# 1-voice_3_3.net
KiCad netlist of a schematic drawn in EAGLE
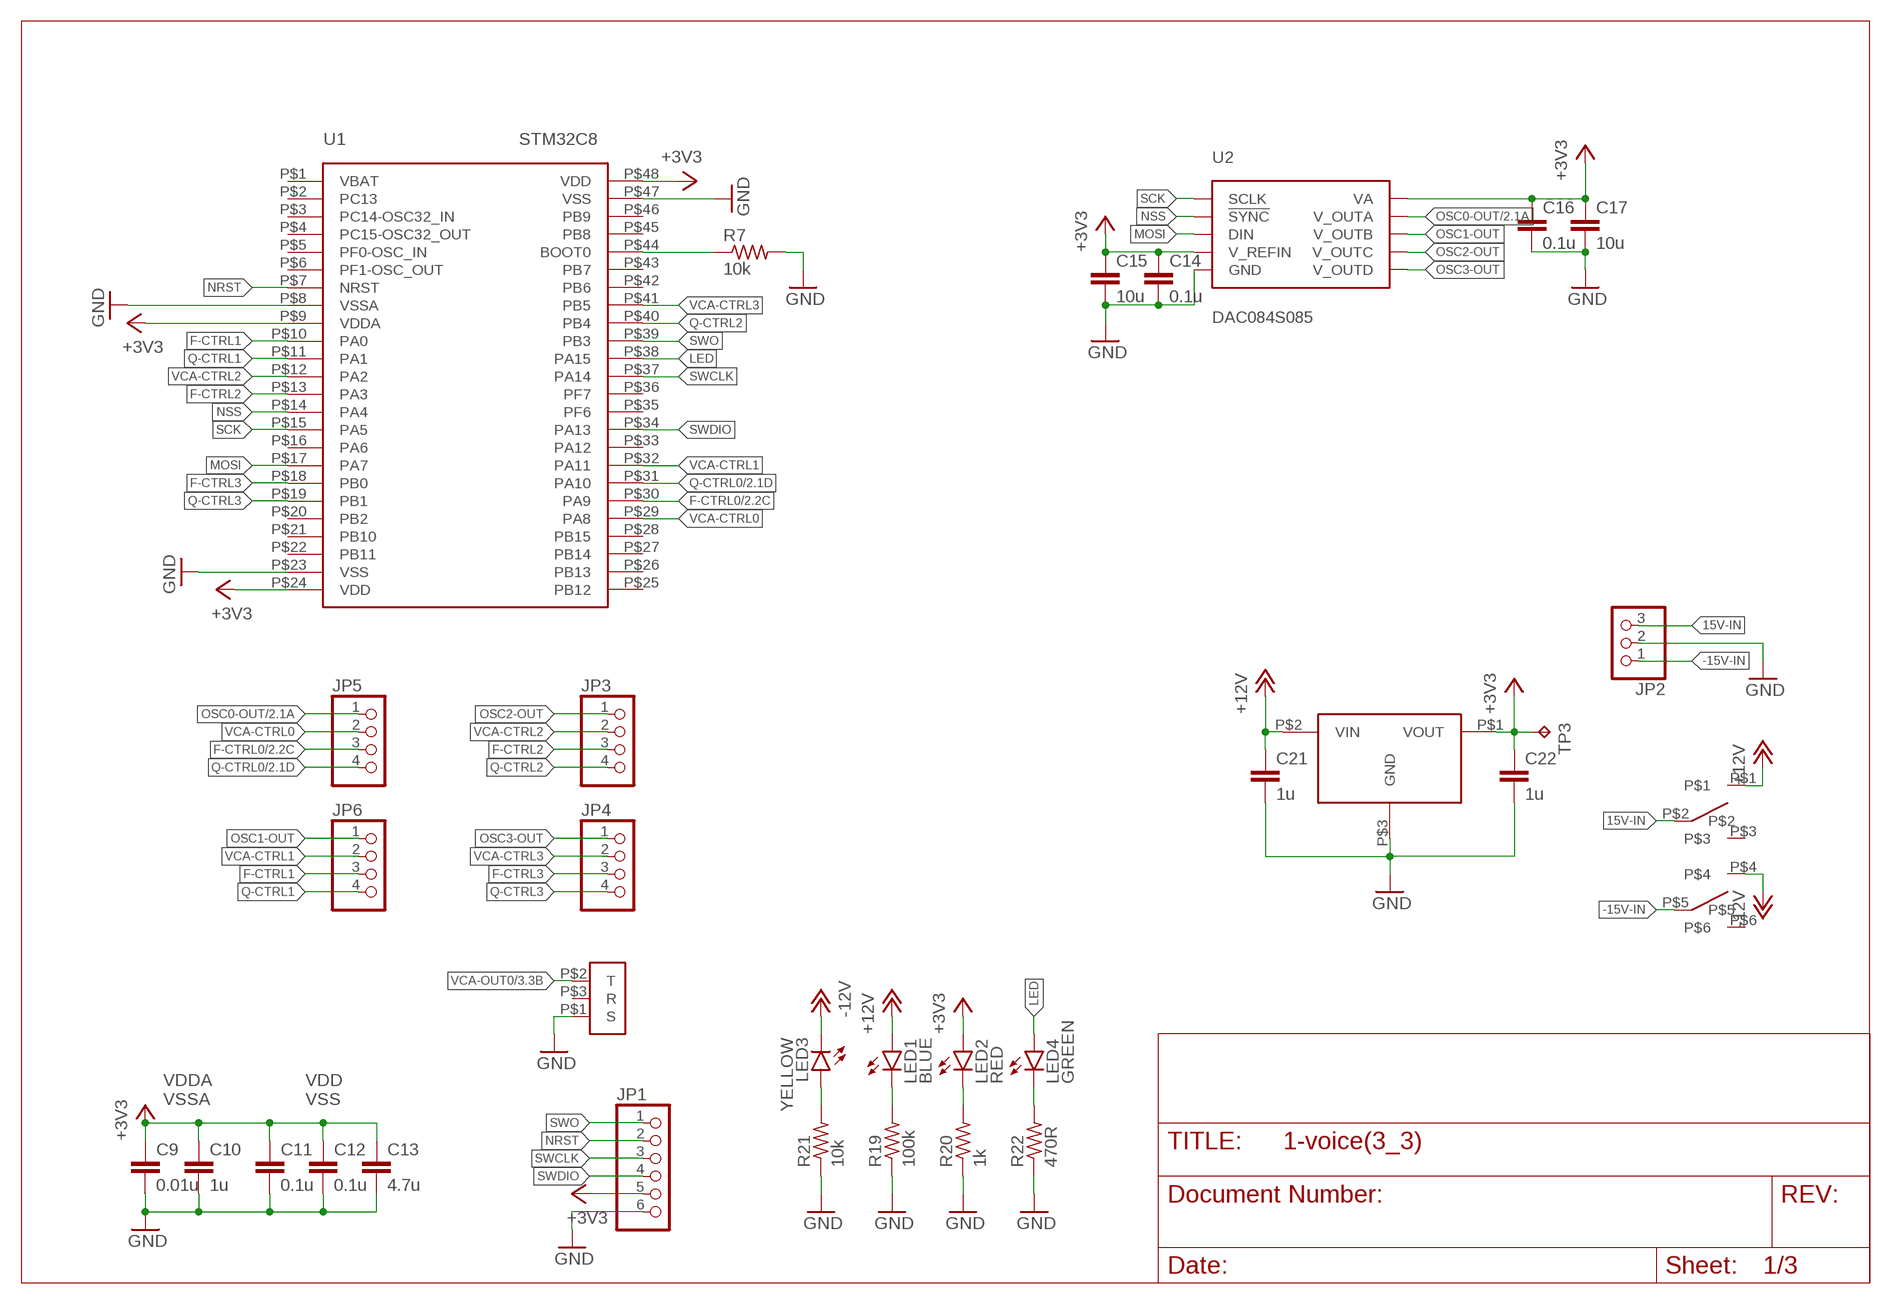
[diagram p0: schematic, sheet 1]
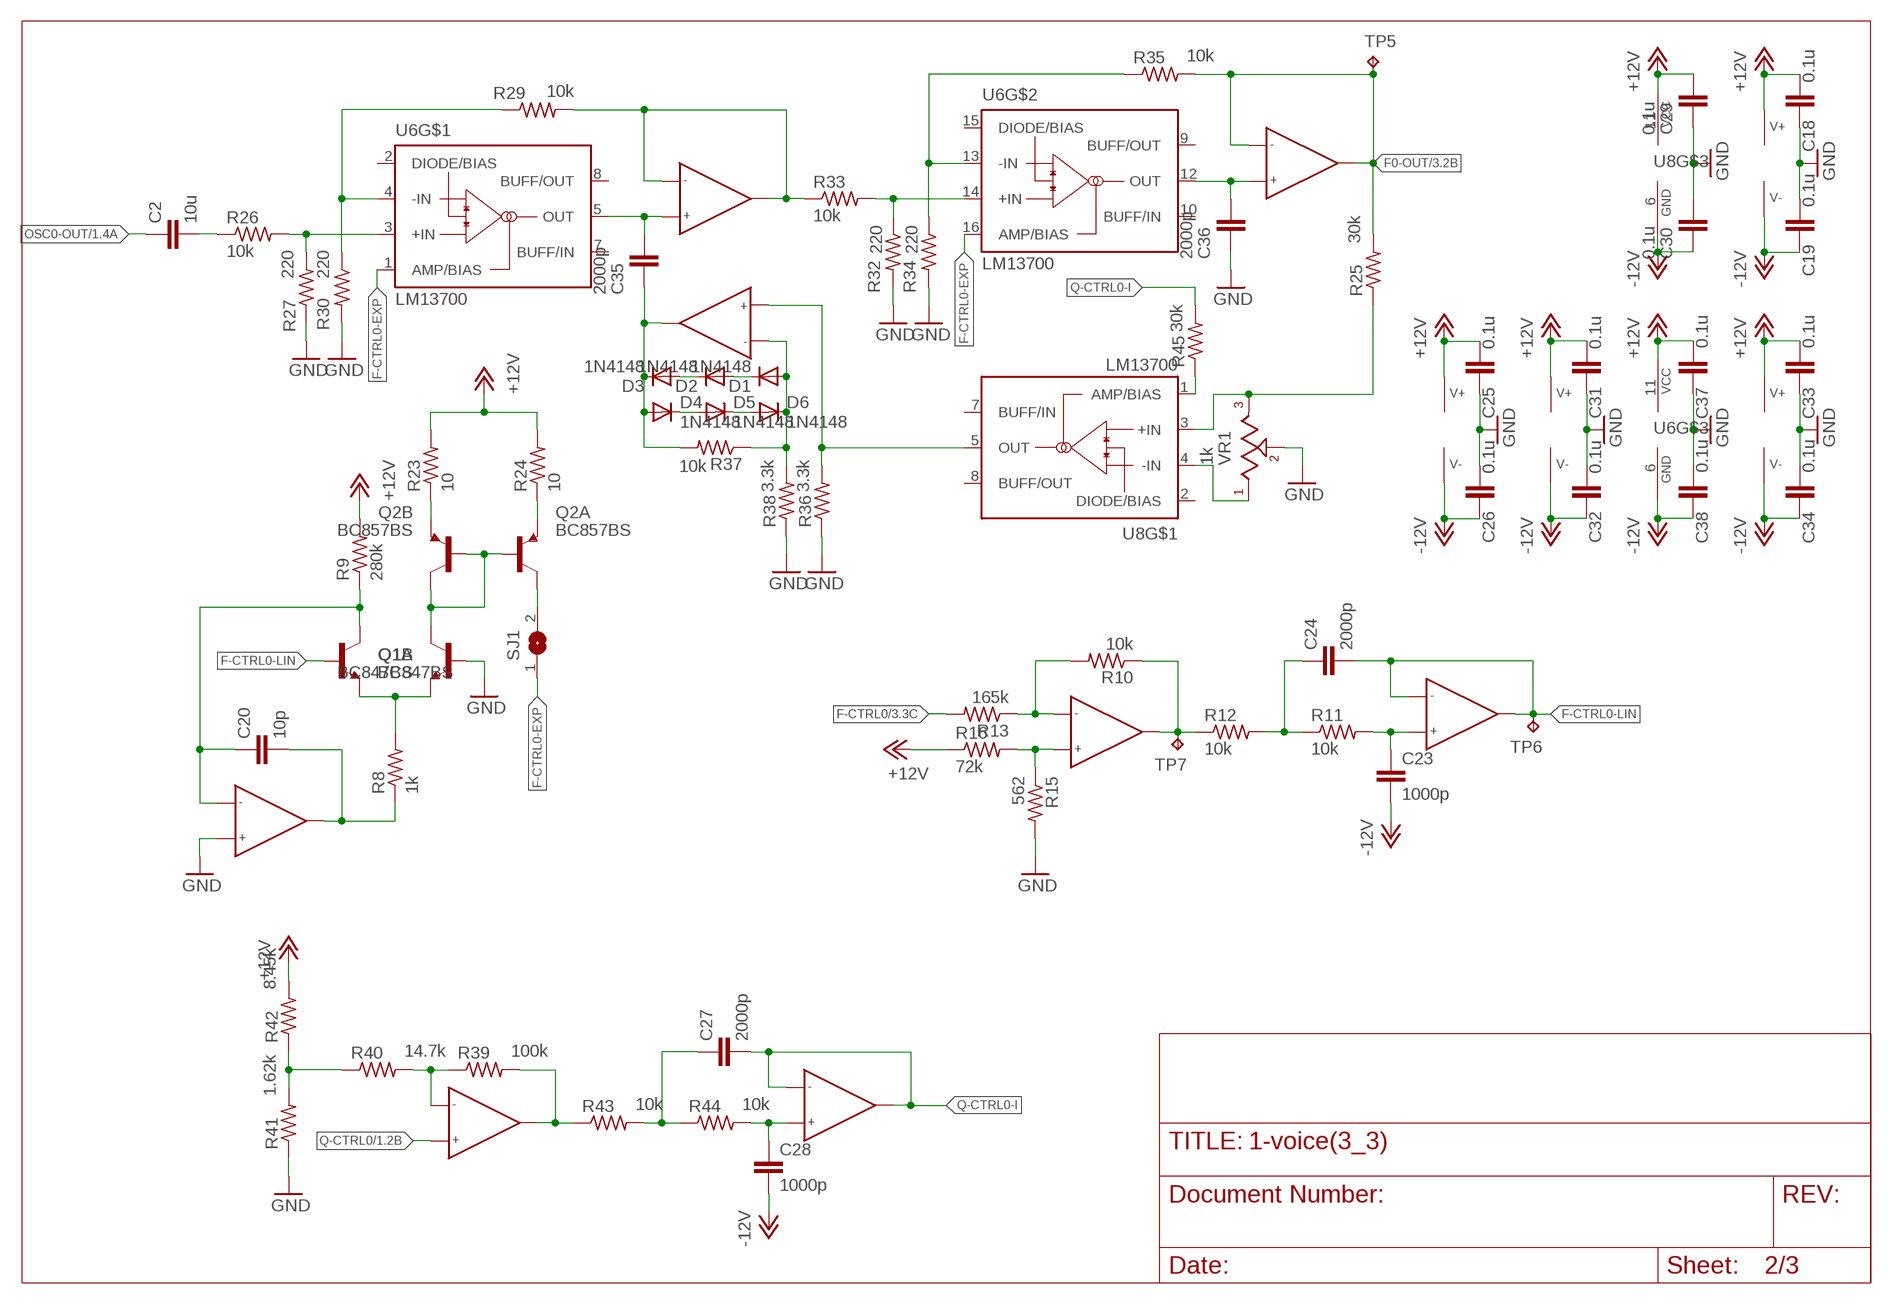
[diagram p1: schematic, sheet 2]
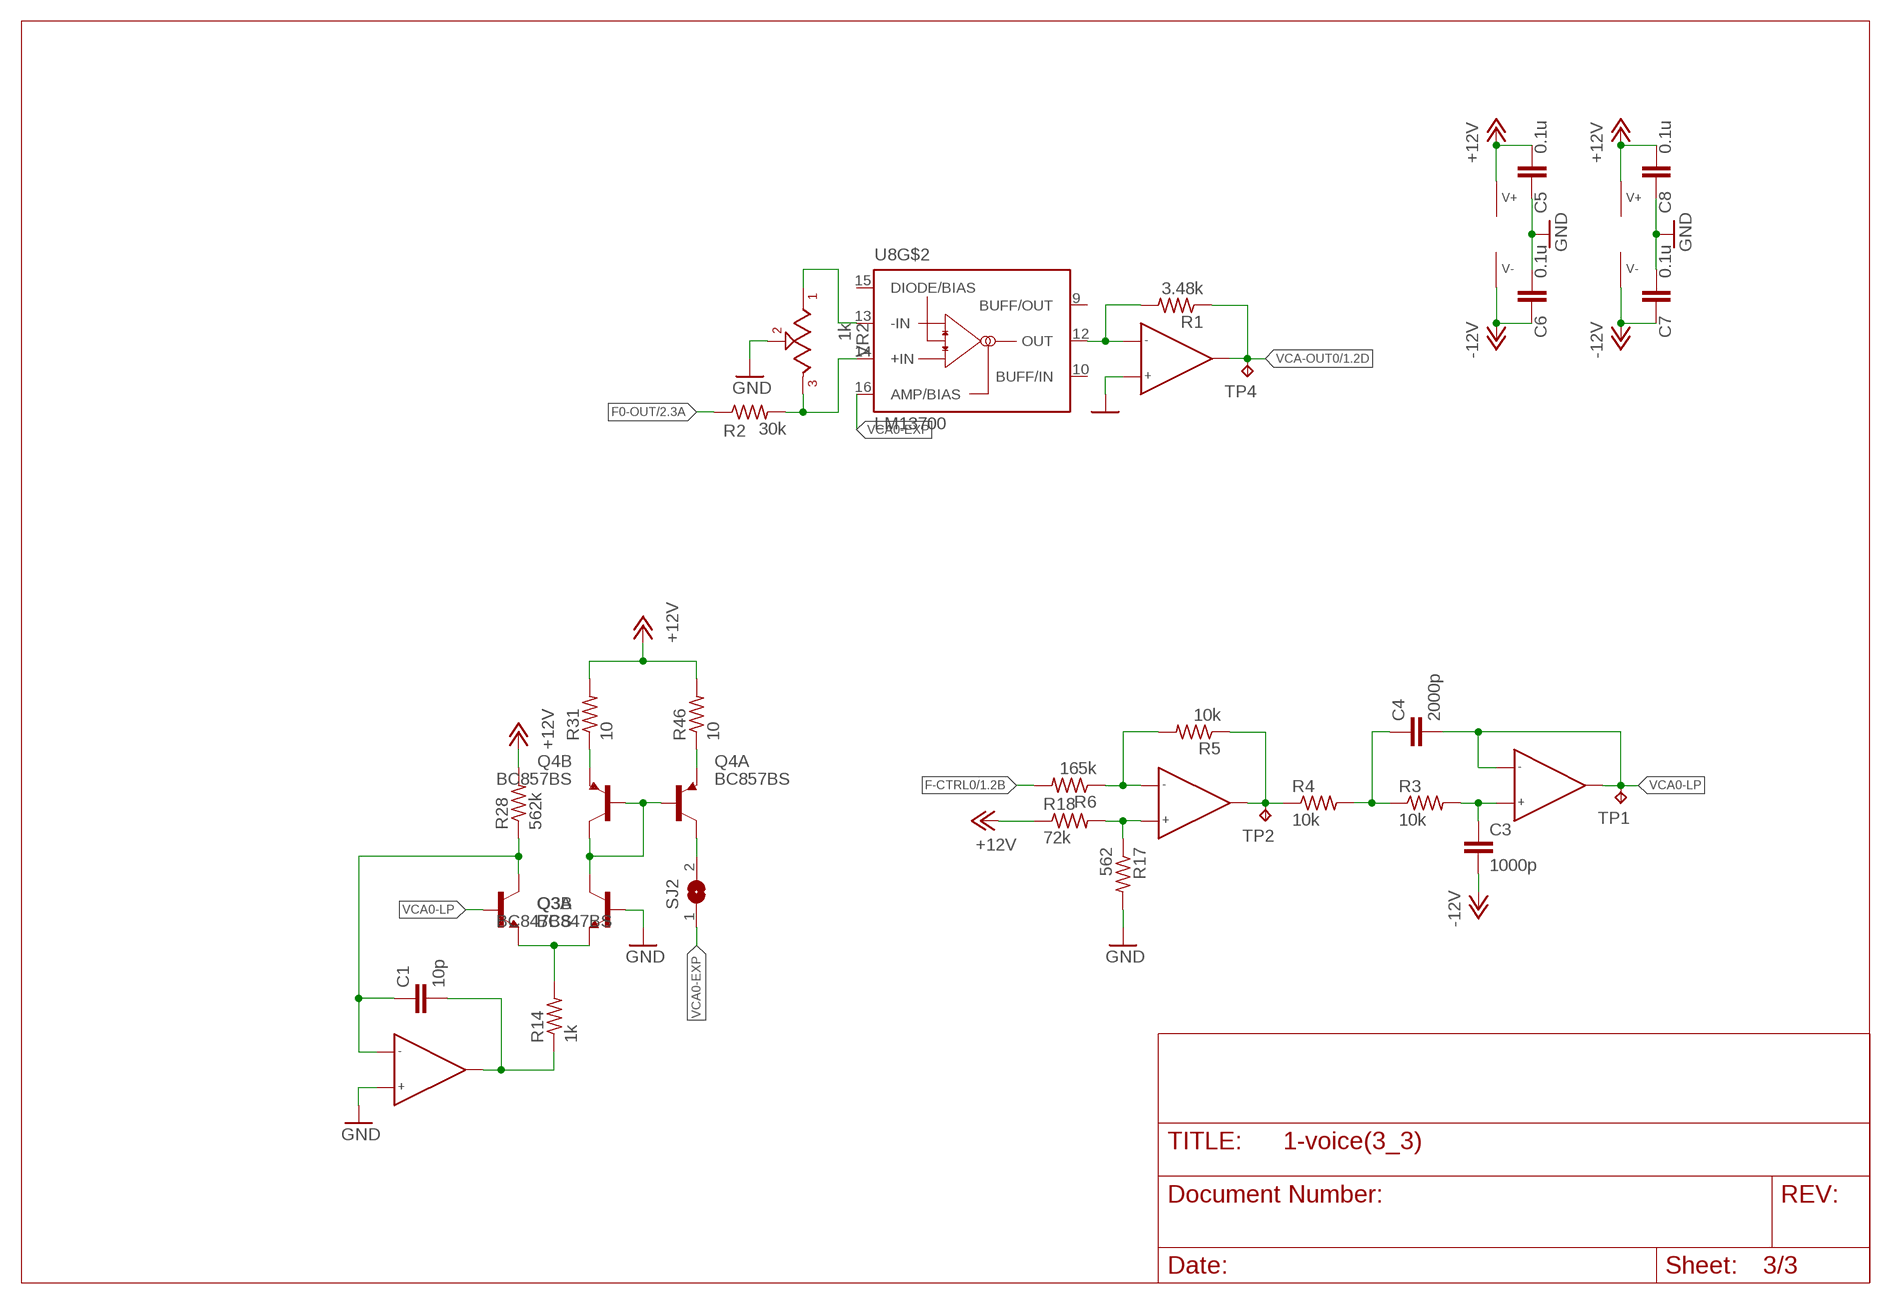
[diagram p2: schematic, sheet 3]

(export (version "E")
  (design (tool "Eeschema 10.0.6"))
  (components
    (comp (ref "C2")
      (value "10u")
      (footprint "eagle-import:C0603")
      (libsource (lib "eagle-import") (part "C-EUC0603"))
    )
    (comp (ref "C18")
      (value "0.1u")
      (footprint "eagle-import:C0603")
      (libsource (lib "eagle-import") (part "C-EUC0603"))
    )
    (comp (ref "C19")
      (value "0.1u")
      (footprint "eagle-import:C0603")
      (libsource (lib "eagle-import") (part "C-EUC0603"))
    )
    (comp (ref "C20")
      (value "10p")
      (footprint "eagle-import:C0603")
      (libsource (lib "eagle-import") (part "C-EUC0603"))
    )
    (comp (ref "C23")
      (value "1000p")
      (footprint "eagle-import:C0603")
      (libsource (lib "eagle-import") (part "C-EUC0603"))
    )
    (comp (ref "C24")
      (value "2000p")
      (footprint "eagle-import:C0603")
      (libsource (lib "eagle-import") (part "C-EUC0603"))
    )
    (comp (ref "C25")
      (value "0.1u")
      (footprint "eagle-import:C0603")
      (libsource (lib "eagle-import") (part "C-EUC0603"))
    )
    (comp (ref "C26")
      (value "0.1u")
      (footprint "eagle-import:C0603")
      (libsource (lib "eagle-import") (part "C-EUC0603"))
    )
    (comp (ref "C27")
      (value "2000p")
      (footprint "eagle-import:C0603")
      (libsource (lib "eagle-import") (part "C-EUC0603"))
    )
    (comp (ref "C28")
      (value "1000p")
      (footprint "eagle-import:C0603")
      (libsource (lib "eagle-import") (part "C-EUC0603"))
    )
    (comp (ref "C29")
      (value "0.1u")
      (footprint "eagle-import:C0603")
      (libsource (lib "eagle-import") (part "C-EUC0603"))
    )
    (comp (ref "C30")
      (value "0.1u")
      (footprint "eagle-import:C0603")
      (libsource (lib "eagle-import") (part "C-EUC0603"))
    )
    (comp (ref "C31")
      (value "0.1u")
      (footprint "eagle-import:C0603")
      (libsource (lib "eagle-import") (part "C-EUC0603"))
    )
    (comp (ref "C32")
      (value "0.1u")
      (footprint "eagle-import:C0603")
      (libsource (lib "eagle-import") (part "C-EUC0603"))
    )
    (comp (ref "C33")
      (value "0.1u")
      (footprint "eagle-import:C0603")
      (libsource (lib "eagle-import") (part "C-EUC0603"))
    )
    (comp (ref "C34")
      (value "0.1u")
      (footprint "eagle-import:C0603")
      (libsource (lib "eagle-import") (part "C-EUC0603"))
    )
    (comp (ref "C35")
      (value "2000p")
      (footprint "eagle-import:C0603")
      (libsource (lib "eagle-import") (part "C-EUC0603"))
    )
    (comp (ref "C36")
      (value "2000p")
      (footprint "eagle-import:C0603")
      (libsource (lib "eagle-import") (part "C-EUC0603"))
    )
    (comp (ref "C37")
      (value "0.1u")
      (footprint "eagle-import:C0603")
      (libsource (lib "eagle-import") (part "C-EUC0603"))
    )
    (comp (ref "C38")
      (value "0.1u")
      (footprint "eagle-import:C0603")
      (libsource (lib "eagle-import") (part "C-EUC0603"))
    )
    (comp (ref "D1")
      (value "1N4148")
      (footprint "eagle-import:SOD123")
      (libsource (lib "eagle-import") (part "DIODESOD123"))
    )
    (comp (ref "D2")
      (value "1N4148")
      (footprint "eagle-import:SOD123")
      (libsource (lib "eagle-import") (part "DIODESOD123"))
    )
    (comp (ref "D3")
      (value "1N4148")
      (footprint "eagle-import:SOD123")
      (libsource (lib "eagle-import") (part "DIODESOD123"))
    )
    (comp (ref "D4")
      (value "1N4148")
      (footprint "eagle-import:SOD123")
      (libsource (lib "eagle-import") (part "DIODESOD123"))
    )
    (comp (ref "D5")
      (value "1N4148")
      (footprint "eagle-import:SOD123")
      (libsource (lib "eagle-import") (part "DIODESOD123"))
    )
    (comp (ref "D6")
      (value "1N4148")
      (footprint "eagle-import:SOD123")
      (libsource (lib "eagle-import") (part "DIODESOD123"))
    )
    (comp (ref "Q1")
      (value "BC847BS")
      (footprint "eagle-import:SOT-363-JBLMASK")
      (fields (field (name "SPICEPREFIX") "Q"))
      (libsource (lib "eagle-import") (part "TRANS-BJT_NPN-DUAL-BC847BS-JBLMASK"))
    )
    (comp (ref "Q2")
      (value "BC857BS")
      (footprint "eagle-import:SOT-363-JBLMASK")
      (fields (field (name "SPICEPREFIX") "Q"))
      (libsource (lib "eagle-import") (part "TRANS-BJT_PNP-DUAL-BC857-JBLMASK"))
    )
    (comp (ref "R8")
      (value "1k")
      (footprint "eagle-import:R0603")
      (libsource (lib "eagle-import") (part "R-US_R0603"))
    )
    (comp (ref "R9")
      (value "280k")
      (footprint "eagle-import:R0603")
      (libsource (lib "eagle-import") (part "R-US_R0603"))
    )
    (comp (ref "R10")
      (value "10k")
      (footprint "eagle-import:R0603")
      (libsource (lib "eagle-import") (part "R-US_R0603"))
    )
    (comp (ref "R11")
      (value "10k")
      (footprint "eagle-import:R0603")
      (libsource (lib "eagle-import") (part "R-US_R0603"))
    )
    (comp (ref "R12")
      (value "10k")
      (footprint "eagle-import:R0603")
      (libsource (lib "eagle-import") (part "R-US_R0603"))
    )
    (comp (ref "R13")
      (value "165k")
      (footprint "eagle-import:R0603")
      (libsource (lib "eagle-import") (part "R-US_R0603"))
    )
    (comp (ref "R15")
      (value "562")
      (footprint "eagle-import:R0603")
      (libsource (lib "eagle-import") (part "R-US_R0603"))
    )
    (comp (ref "R16")
      (value "72k")
      (footprint "eagle-import:R0603")
      (libsource (lib "eagle-import") (part "R-US_R0603"))
    )
    (comp (ref "R23")
      (value "10")
      (footprint "eagle-import:R0603")
      (libsource (lib "eagle-import") (part "R-US_R0603"))
    )
    (comp (ref "R24")
      (value "10")
      (footprint "eagle-import:R0603")
      (libsource (lib "eagle-import") (part "R-US_R0603"))
    )
    (comp (ref "R25")
      (value "30k")
      (footprint "eagle-import:R0603")
      (libsource (lib "eagle-import") (part "R-US_R0603"))
    )
    (comp (ref "R26")
      (value "10k")
      (footprint "eagle-import:R0603")
      (libsource (lib "eagle-import") (part "R-US_R0603"))
    )
    (comp (ref "R27")
      (value "220")
      (footprint "eagle-import:R0603")
      (libsource (lib "eagle-import") (part "R-US_R0603"))
    )
    (comp (ref "R29")
      (value "10k")
      (footprint "eagle-import:R0603")
      (libsource (lib "eagle-import") (part "R-US_R0603"))
    )
    (comp (ref "R30")
      (value "220")
      (footprint "eagle-import:R0603")
      (libsource (lib "eagle-import") (part "R-US_R0603"))
    )
    (comp (ref "R32")
      (value "220")
      (footprint "eagle-import:R0603")
      (libsource (lib "eagle-import") (part "R-US_R0603"))
    )
    (comp (ref "R33")
      (value "10k")
      (footprint "eagle-import:R0603")
      (libsource (lib "eagle-import") (part "R-US_R0603"))
    )
    (comp (ref "R34")
      (value "220")
      (footprint "eagle-import:R0603")
      (libsource (lib "eagle-import") (part "R-US_R0603"))
    )
    (comp (ref "R35")
      (value "10k")
      (footprint "eagle-import:R0603")
      (libsource (lib "eagle-import") (part "R-US_R0603"))
    )
    (comp (ref "R36")
      (value "3.3k")
      (footprint "eagle-import:R0603")
      (libsource (lib "eagle-import") (part "R-US_R0603"))
    )
    (comp (ref "R37")
      (value "10k")
      (footprint "eagle-import:R0603")
      (libsource (lib "eagle-import") (part "R-US_R0603"))
    )
    (comp (ref "R38")
      (value "3.3k")
      (footprint "eagle-import:R0603")
      (libsource (lib "eagle-import") (part "R-US_R0603"))
    )
    (comp (ref "R39")
      (value "100k")
      (footprint "eagle-import:R0603")
      (libsource (lib "eagle-import") (part "R-US_R0603"))
    )
    (comp (ref "R40")
      (value "14.7k")
      (footprint "eagle-import:R0603")
      (libsource (lib "eagle-import") (part "R-US_R0603"))
    )
    (comp (ref "R41")
      (value "1.62k")
      (footprint "eagle-import:R0603")
      (libsource (lib "eagle-import") (part "R-US_R0603"))
    )
    (comp (ref "R42")
      (value "8.45k")
      (footprint "eagle-import:R0603")
      (libsource (lib "eagle-import") (part "R-US_R0603"))
    )
    (comp (ref "R43")
      (value "10k")
      (footprint "eagle-import:R0603")
      (libsource (lib "eagle-import") (part "R-US_R0603"))
    )
    (comp (ref "R44")
      (value "10k")
      (footprint "eagle-import:R0603")
      (libsource (lib "eagle-import") (part "R-US_R0603"))
    )
    (comp (ref "R45")
      (value "30k")
      (footprint "eagle-import:R0603")
      (libsource (lib "eagle-import") (part "R-US_R0603"))
    )
    (comp (ref "SJ1")
      (value "SJ")
      (footprint "eagle-import:SJ")
      (fields (field (name "SPICEPREFIX") "B"))
      (libsource (lib "eagle-import") (part "SJ"))
    )
    (comp (ref "TP5")
      (value "TPPAD1-13")
      (footprint "eagle-import:P1-13")
      (libsource (lib "eagle-import") (part "TPPAD1-13"))
    )
    (comp (ref "TP6")
      (value "TPPAD1-13")
      (footprint "eagle-import:P1-13")
      (libsource (lib "eagle-import") (part "TPPAD1-13"))
    )
    (comp (ref "TP7")
      (value "TPPAD1-13")
      (footprint "eagle-import:P1-13")
      (libsource (lib "eagle-import") (part "TPPAD1-13"))
    )
    (comp (ref "U4")
      (value "TL072")
      (footprint "eagle-import:SOIC8")
      (libsource (lib "eagle-import") (part "TL072"))
    )
    (comp (ref "U5")
      (value "TL072")
      (footprint "eagle-import:SOIC8")
      (libsource (lib "eagle-import") (part "TL072"))
    )
    (comp (ref "U6")
      (value "LM13700")
      (footprint "eagle-import:DMP16")
      (libsource (lib "eagle-import") (part "XX-13700DMP16"))
    )
    (comp (ref "U7")
      (value "TL072")
      (footprint "eagle-import:SOIC8")
      (libsource (lib "eagle-import") (part "TL072"))
    )
    (comp (ref "U8")
      (value "LM13700")
      (footprint "eagle-import:DMP16")
      (libsource (lib "eagle-import") (part "XX-13700DMP16"))
    )
    (comp (ref "U9")
      (value "TL072")
      (footprint "eagle-import:SOIC8")
      (fields (field (name "SPICEPREFIX") "U"))
      (libsource (lib "eagle-import") (part "TL072"))
    )
    (comp (ref "VR1")
      (value "1k")
      (footprint "eagle-import:POT-TRIM-SMD-BOURNS-3314")
      (libsource (lib "eagle-import") (part "POT-TRIM-SMD-BOURNS-3314J-1"))
    )
    (comp (ref "C1")
      (value "10p")
      (footprint "eagle-import:C0603")
      (libsource (lib "eagle-import") (part "C-EUC0603"))
    )
    (comp (ref "C3")
      (value "1000p")
      (footprint "eagle-import:C0603")
      (libsource (lib "eagle-import") (part "C-EUC0603"))
    )
    (comp (ref "C4")
      (value "2000p")
      (footprint "eagle-import:C0603")
      (libsource (lib "eagle-import") (part "C-EUC0603"))
    )
    (comp (ref "C5")
      (value "0.1u")
      (footprint "eagle-import:C0603")
      (libsource (lib "eagle-import") (part "C-EUC0603"))
    )
    (comp (ref "C6")
      (value "0.1u")
      (footprint "eagle-import:C0603")
      (libsource (lib "eagle-import") (part "C-EUC0603"))
    )
    (comp (ref "C7")
      (value "0.1u")
      (footprint "eagle-import:C0603")
      (libsource (lib "eagle-import") (part "C-EUC0603"))
    )
    (comp (ref "C8")
      (value "0.1u")
      (footprint "eagle-import:C0603")
      (libsource (lib "eagle-import") (part "C-EUC0603"))
    )
    (comp (ref "Q3")
      (value "BC847BS")
      (footprint "eagle-import:SOT-363-JBLMASK")
      (fields (field (name "SPICEPREFIX") "Q"))
      (libsource (lib "eagle-import") (part "TRANS-BJT_NPN-DUAL-BC847BS-JBLMASK"))
    )
    (comp (ref "Q4")
      (value "BC857BS")
      (footprint "eagle-import:SOT-363-JBLMASK")
      (fields (field (name "SPICEPREFIX") "Q"))
      (libsource (lib "eagle-import") (part "TRANS-BJT_PNP-DUAL-BC857-JBLMASK"))
    )
    (comp (ref "R1")
      (value "3.48k")
      (footprint "eagle-import:R0603")
      (libsource (lib "eagle-import") (part "R-US_R0603"))
    )
    (comp (ref "R2")
      (value "30k")
      (footprint "eagle-import:R0603")
      (libsource (lib "eagle-import") (part "R-US_R0603"))
    )
    (comp (ref "R3")
      (value "10k")
      (footprint "eagle-import:R0603")
      (libsource (lib "eagle-import") (part "R-US_R0603"))
    )
    (comp (ref "R4")
      (value "10k")
      (footprint "eagle-import:R0603")
      (libsource (lib "eagle-import") (part "R-US_R0603"))
    )
    (comp (ref "R5")
      (value "10k")
      (footprint "eagle-import:R0603")
      (libsource (lib "eagle-import") (part "R-US_R0603"))
    )
    (comp (ref "R6")
      (value "165k")
      (footprint "eagle-import:R0603")
      (libsource (lib "eagle-import") (part "R-US_R0603"))
    )
    (comp (ref "R14")
      (value "1k")
      (footprint "eagle-import:R0603")
      (libsource (lib "eagle-import") (part "R-US_R0603"))
    )
    (comp (ref "R17")
      (value "562")
      (footprint "eagle-import:R0603")
      (libsource (lib "eagle-import") (part "R-US_R0603"))
    )
    (comp (ref "R18")
      (value "72k")
      (footprint "eagle-import:R0603")
      (libsource (lib "eagle-import") (part "R-US_R0603"))
    )
    (comp (ref "R28")
      (value "562k")
      (footprint "eagle-import:R0603")
      (libsource (lib "eagle-import") (part "R-US_R0603"))
    )
    (comp (ref "R31")
      (value "10")
      (footprint "eagle-import:R0603")
      (libsource (lib "eagle-import") (part "R-US_R0603"))
    )
    (comp (ref "R46")
      (value "10")
      (footprint "eagle-import:R0603")
      (libsource (lib "eagle-import") (part "R-US_R0603"))
    )
    (comp (ref "SJ2")
      (value "SJ")
      (footprint "eagle-import:SJ")
      (fields (field (name "SPICEPREFIX") "B"))
      (libsource (lib "eagle-import") (part "SJ"))
    )
    (comp (ref "TP1")
      (value "TPPAD1-13")
      (footprint "eagle-import:P1-13")
      (libsource (lib "eagle-import") (part "TPPAD1-13"))
    )
    (comp (ref "TP2")
      (value "TPPAD1-13")
      (footprint "eagle-import:P1-13")
      (libsource (lib "eagle-import") (part "TPPAD1-13"))
    )
    (comp (ref "TP4")
      (value "TPPAD1-13")
      (footprint "eagle-import:P1-13")
      (libsource (lib "eagle-import") (part "TPPAD1-13"))
    )
    (comp (ref "U10")
      (value "TL072")
      (footprint "eagle-import:SOIC8")
      (libsource (lib "eagle-import") (part "TL072"))
    )
    (comp (ref "U11")
      (value "TL072")
      (footprint "eagle-import:SOIC8")
      (libsource (lib "eagle-import") (part "TL072"))
    )
    (comp (ref "VR2")
      (value "1k")
      (footprint "eagle-import:POT-TRIM-SMD-BOURNS-3314")
      (libsource (lib "eagle-import") (part "POT-TRIM-SMD-BOURNS-3314J-1"))
    )
    (comp (ref "C9")
      (value "0.01u")
      (footprint "eagle-import:C0603")
      (libsource (lib "eagle-import") (part "C-EUC0603"))
    )
    (comp (ref "C10")
      (value "1u")
      (footprint "eagle-import:C0603")
      (libsource (lib "eagle-import") (part "C-EUC0603"))
    )
    (comp (ref "C11")
      (value "0.1u")
      (footprint "eagle-import:C0603")
      (libsource (lib "eagle-import") (part "C-EUC0603"))
    )
    (comp (ref "C12")
      (value "0.1u")
      (footprint "eagle-import:C0603")
      (libsource (lib "eagle-import") (part "C-EUC0603"))
    )
    (comp (ref "C13")
      (value "4.7u")
      (footprint "eagle-import:C0603")
      (libsource (lib "eagle-import") (part "C-EUC0603"))
    )
    (comp (ref "C14")
      (value "0.1u")
      (footprint "eagle-import:C0603")
      (libsource (lib "eagle-import") (part "C-EUC0603"))
    )
    (comp (ref "C15")
      (value "10u")
      (footprint "eagle-import:C0603")
      (libsource (lib "eagle-import") (part "C-EUC0603"))
    )
    (comp (ref "C16")
      (value "0.1u")
      (footprint "eagle-import:C0603")
      (libsource (lib "eagle-import") (part "C-EUC0603"))
    )
    (comp (ref "C17")
      (value "10u")
      (footprint "eagle-import:C0603")
      (libsource (lib "eagle-import") (part "C-EUC0603"))
    )
    (comp (ref "C21")
      (value "1u")
      (footprint "eagle-import:C0603")
      (libsource (lib "eagle-import") (part "C-EUC0603"))
    )
    (comp (ref "C22")
      (value "1u")
      (footprint "eagle-import:C0603")
      (libsource (lib "eagle-import") (part "C-EUC0603"))
    )
    (comp (ref "JP1")
      (value "PINHD-1X6")
      (footprint "eagle-import:1X06")
      (libsource (lib "eagle-import") (part "PINHD-1X6"))
    )
    (comp (ref "JP2")
      (value "PINHD-1X3")
      (footprint "eagle-import:1X03")
      (libsource (lib "eagle-import") (part "PINHD-1X3"))
    )
    (comp (ref "JP3")
      (value "PINHD-1X4")
      (footprint "eagle-import:1X04")
      (libsource (lib "eagle-import") (part "PINHD-1X4"))
    )
    (comp (ref "JP4")
      (value "PINHD-1X4")
      (footprint "eagle-import:1X04")
      (libsource (lib "eagle-import") (part "PINHD-1X4"))
    )
    (comp (ref "JP5")
      (value "PINHD-1X4")
      (footprint "eagle-import:1X04")
      (libsource (lib "eagle-import") (part "PINHD-1X4"))
    )
    (comp (ref "JP6")
      (value "PINHD-1X4")
      (footprint "eagle-import:1X04")
      (libsource (lib "eagle-import") (part "PINHD-1X4"))
    )
    (comp (ref "JP7")
      (value "TRS")
      (footprint "eagle-import:TRS")
      (libsource (lib "eagle-import") (part "TRS"))
    )
    (comp (ref "LED1")
      (value "BLUE")
      (footprint "eagle-import:1206")
      (libsource (lib "eagle-import") (part "LEDSMT1206"))
    )
    (comp (ref "LED2")
      (value "RED")
      (footprint "eagle-import:1206")
      (libsource (lib "eagle-import") (part "LEDSMT1206"))
    )
    (comp (ref "LED3")
      (value "YELLOW")
      (footprint "eagle-import:1206")
      (libsource (lib "eagle-import") (part "LEDSMT1206"))
    )
    (comp (ref "LED4")
      (value "GREEN")
      (footprint "eagle-import:1206")
      (libsource (lib "eagle-import") (part "LEDSMT1206"))
    )
    (comp (ref "R7")
      (value "10k")
      (footprint "eagle-import:R0603")
      (libsource (lib "eagle-import") (part "R-US_R0603"))
    )
    (comp (ref "R19")
      (value "100k")
      (footprint "eagle-import:R0603")
      (libsource (lib "eagle-import") (part "R-US_R0603"))
    )
    (comp (ref "R20")
      (value "1k")
      (footprint "eagle-import:R0603")
      (libsource (lib "eagle-import") (part "R-US_R0603"))
    )
    (comp (ref "R21")
      (value "10k")
      (footprint "eagle-import:R0603")
      (libsource (lib "eagle-import") (part "R-US_R0603"))
    )
    (comp (ref "R22")
      (value "470R")
      (footprint "eagle-import:R0603")
      (libsource (lib "eagle-import") (part "R-US_R0603"))
    )
    (comp (ref "SW1")
      (value "SWITCH-DPDT")
      (footprint "eagle-import:DPDT")
      (libsource (lib "eagle-import") (part "SWITCH-DPDT"))
    )
    (comp (ref "TP3")
      (value "TPPAD1-13")
      (footprint "eagle-import:P1-13")
      (libsource (lib "eagle-import") (part "TPPAD1-13"))
    )
    (comp (ref "U1")
      (value "STM32C8")
      (footprint "eagle-import:LQFP48")
      (libsource (lib "eagle-import") (part "STM32C8"))
    )
    (comp (ref "U2")
      (value "DAC084S085")
      (footprint "eagle-import:VSSOP10")
      (libsource (lib "eagle-import") (part "DAC084S085"))
    )
    (comp (ref "U3")
      (value "TLV760")
      (footprint "eagle-import:SOT23-3")
      (libsource (lib "eagle-import") (part "TLV760"))
    )
  )
  (nets
    (net (code "1") (name "+3V3") (class "Default")
      (node (ref "C10") (pin "1") (pinfunction "1_1") (pintype "passive"))
      (node (ref "C11") (pin "1") (pinfunction "1_1") (pintype "passive"))
      (node (ref "C12") (pin "1") (pinfunction "1_1") (pintype "passive"))
      (node (ref "C13") (pin "1") (pinfunction "1_1") (pintype "passive"))
      (node (ref "C14") (pin "1") (pinfunction "1_1") (pintype "passive"))
      (node (ref "C15") (pin "1") (pinfunction "1_1") (pintype "passive"))
      (node (ref "C16") (pin "1") (pinfunction "1_1") (pintype "passive"))
      (node (ref "C17") (pin "1") (pinfunction "1_1") (pintype "passive"))
      (node (ref "C22") (pin "1") (pinfunction "1_1") (pintype "passive"))
      (node (ref "C9") (pin "1") (pinfunction "1_1") (pintype "passive"))
      (node (ref "JP1") (pin "5") (pinfunction "5_5") (pintype "passive"))
      (node (ref "LED2") (pin "A") (pinfunction "A_A") (pintype "passive"))
      (node (ref "TP3") (pin "TP") (pinfunction "TP_TP") (pintype "input"))
      (node (ref "U1") (pin "P$24") (pinfunction "VDD_P$24") (pintype "bidirectional"))
      (node (ref "U1") (pin "P$48") (pinfunction "VDD_P$48") (pintype "bidirectional"))
      (node (ref "U1") (pin "P$9") (pinfunction "VDDA_P$9") (pintype "bidirectional"))
      (node (ref "U2") (pin "P$1") (pinfunction "VA_P$1") (pintype "bidirectional"))
      (node (ref "U2") (pin "P$7") (pinfunction "V_REFIN_P$7") (pintype "bidirectional"))
      (node (ref "U3") (pin "P$1") (pinfunction "VOUT_P$1") (pintype "bidirectional"))
    )
    (net (code "2") (name "+12V") (class "Default")
      (node (ref "C18") (pin "2") (pinfunction "2_2") (pintype "passive"))
      (node (ref "C21") (pin "1") (pinfunction "1_1") (pintype "passive"))
      (node (ref "C25") (pin "2") (pinfunction "2_2") (pintype "passive"))
      (node (ref "C29") (pin "1") (pinfunction "1_1") (pintype "passive"))
      (node (ref "C31") (pin "2") (pinfunction "2_2") (pintype "passive"))
      (node (ref "C33") (pin "1") (pinfunction "1_1") (pintype "passive"))
      (node (ref "C37") (pin "1") (pinfunction "1_1") (pintype "passive"))
      (node (ref "C5") (pin "2") (pinfunction "2_2") (pintype "passive"))
      (node (ref "C8") (pin "2") (pinfunction "2_2") (pintype "passive"))
      (node (ref "LED1") (pin "A") (pinfunction "A_A") (pintype "passive"))
      (node (ref "R16") (pin "1") (pinfunction "1_1") (pintype "passive"))
      (node (ref "R18") (pin "1") (pinfunction "1_1") (pintype "passive"))
      (node (ref "R23") (pin "2") (pinfunction "2_2") (pintype "passive"))
      (node (ref "R24") (pin "2") (pinfunction "2_2") (pintype "passive"))
      (node (ref "R28") (pin "2") (pinfunction "2_2") (pintype "passive"))
      (node (ref "R31") (pin "2") (pinfunction "2_2") (pintype "passive"))
      (node (ref "R42") (pin "2") (pinfunction "2_2") (pintype "passive"))
      (node (ref "R46") (pin "2") (pinfunction "2_2") (pintype "passive"))
      (node (ref "R9") (pin "2") (pinfunction "2_2") (pintype "passive"))
      (node (ref "SW1") (pin "P$1") (pinfunction "P$1_P$1") (pintype "bidirectional"))
      (node (ref "U10") (pin "P$8") (pinfunction "V+_P$8") (pintype "bidirectional"))
      (node (ref "U11") (pin "P$8") (pinfunction "V+_P$8") (pintype "bidirectional"))
      (node (ref "U3") (pin "P$2") (pinfunction "VIN_P$2") (pintype "bidirectional"))
      (node (ref "U4") (pin "P$8") (pinfunction "V+_P$8") (pintype "bidirectional"))
      (node (ref "U5") (pin "P$8") (pinfunction "V+_P$8") (pintype "bidirectional"))
      (node (ref "U6") (pin "11") (pinfunction "VCC_11") (pintype "power_in"))
      (node (ref "U7") (pin "P$8") (pinfunction "V+_P$8") (pintype "bidirectional"))
      (node (ref "U8") (pin "11") (pinfunction "VCC_11") (pintype "power_in"))
      (node (ref "U9") (pin "P$8") (pinfunction "V+_P$8") (pintype "bidirectional"))
    )
    (net (code "3") (name "-12V") (class "Default")
      (node (ref "C19") (pin "1") (pinfunction "1_1") (pintype "passive"))
      (node (ref "C23") (pin "2") (pinfunction "2_2") (pintype "passive"))
      (node (ref "C26") (pin "1") (pinfunction "1_1") (pintype "passive"))
      (node (ref "C28") (pin "2") (pinfunction "2_2") (pintype "passive"))
      (node (ref "C3") (pin "2") (pinfunction "2_2") (pintype "passive"))
      (node (ref "C30") (pin "2") (pinfunction "2_2") (pintype "passive"))
      (node (ref "C32") (pin "1") (pinfunction "1_1") (pintype "passive"))
      (node (ref "C34") (pin "2") (pinfunction "2_2") (pintype "passive"))
      (node (ref "C38") (pin "2") (pinfunction "2_2") (pintype "passive"))
      (node (ref "C6") (pin "1") (pinfunction "1_1") (pintype "passive"))
      (node (ref "C7") (pin "1") (pinfunction "1_1") (pintype "passive"))
      (node (ref "LED3") (pin "C") (pinfunction "C_C") (pintype "passive"))
      (node (ref "SW1") (pin "P$4") (pinfunction "P$4_P$4") (pintype "bidirectional"))
      (node (ref "U10") (pin "P$4") (pinfunction "V-_P$4") (pintype "bidirectional"))
      (node (ref "U11") (pin "P$4") (pinfunction "V-_P$4") (pintype "bidirectional"))
      (node (ref "U4") (pin "P$4") (pinfunction "V-_P$4") (pintype "bidirectional"))
      (node (ref "U5") (pin "P$4") (pinfunction "V-_P$4") (pintype "bidirectional"))
      (node (ref "U6") (pin "6") (pinfunction "GND_6") (pintype "power_in"))
      (node (ref "U7") (pin "P$4") (pinfunction "V-_P$4") (pintype "bidirectional"))
      (node (ref "U8") (pin "6") (pinfunction "GND_6") (pintype "power_in"))
      (node (ref "U9") (pin "P$4") (pinfunction "V-_P$4") (pintype "bidirectional"))
    )
    (net (code "4") (name "-15V-IN") (class "Default")
      (node (ref "JP2") (pin "1") (pinfunction "1_1") (pintype "passive"))
      (node (ref "SW1") (pin "P$5") (pinfunction "P$5_P$5") (pintype "bidirectional"))
    )
    (net (code "5") (name "15V-IN") (class "Default")
      (node (ref "JP2") (pin "3") (pinfunction "3_3") (pintype "passive"))
      (node (ref "SW1") (pin "P$2") (pinfunction "P$2_P$2") (pintype "bidirectional"))
    )
    (net (code "6") (name "F-CTRL0") (class "Default")
      (node (ref "JP5") (pin "3") (pinfunction "3_3") (pintype "passive"))
      (node (ref "R13") (pin "2") (pinfunction "2_2") (pintype "passive"))
      (node (ref "R6") (pin "2") (pinfunction "2_2") (pintype "passive"))
      (node (ref "U1") (pin "P$30") (pinfunction "PA9_P$30") (pintype "bidirectional"))
    )
    (net (code "7") (name "F-CTRL0-EXP") (class "Default")
      (node (ref "SJ1") (pin "1") (pinfunction "1_1") (pintype "passive"))
      (node (ref "U6") (pin "1") (pinfunction "AMP/BIAS_1") (pintype "passive"))
      (node (ref "U6") (pin "16") (pinfunction "AMP/BIAS_16") (pintype "passive"))
    )
    (net (code "8") (name "F-CTRL0-LIN") (class "Default")
      (node (ref "C24") (pin "2") (pinfunction "2_2") (pintype "passive"))
      (node (ref "Q1") (pin "2") (pinfunction "B_2") (pintype "passive"))
      (node (ref "TP6") (pin "TP") (pinfunction "TP_TP") (pintype "input"))
      (node (ref "U4") (pin "P$1") (pinfunction "OUT_P$1") (pintype "bidirectional"))
      (node (ref "U4") (pin "P$2") (pinfunction "IN-_P$2") (pintype "bidirectional"))
    )
    (net (code "9") (name "F-CTRL1") (class "Default")
      (node (ref "JP6") (pin "3") (pinfunction "3_3") (pintype "passive"))
      (node (ref "U1") (pin "P$10") (pinfunction "PA0_P$10") (pintype "bidirectional"))
    )
    (net (code "10") (name "F-CTRL2") (class "Default")
      (node (ref "JP3") (pin "3") (pinfunction "3_3") (pintype "passive"))
      (node (ref "U1") (pin "P$13") (pinfunction "PA3_P$13") (pintype "bidirectional"))
    )
    (net (code "11") (name "F-CTRL3") (class "Default")
      (node (ref "JP4") (pin "3") (pinfunction "3_3") (pintype "passive"))
      (node (ref "U1") (pin "P$18") (pinfunction "PB0_P$18") (pintype "bidirectional"))
    )
    (net (code "12") (name "F0-OUT") (class "Default")
      (node (ref "R2") (pin "1") (pinfunction "1_1") (pintype "passive"))
      (node (ref "R25") (pin "2") (pinfunction "2_2") (pintype "passive"))
      (node (ref "R35") (pin "2") (pinfunction "2_2") (pintype "passive"))
      (node (ref "TP5") (pin "TP") (pinfunction "TP_TP") (pintype "input"))
      (node (ref "U7") (pin "P$6") (pinfunction "IN-_P$6") (pintype "bidirectional"))
      (node (ref "U7") (pin "P$7") (pinfunction "OUT_P$7") (pintype "bidirectional"))
    )
    (net (code "13") (name "GND") (class "Default")
      (node (ref "C10") (pin "2") (pinfunction "2_2") (pintype "passive"))
      (node (ref "C11") (pin "2") (pinfunction "2_2") (pintype "passive"))
      (node (ref "C12") (pin "2") (pinfunction "2_2") (pintype "passive"))
      (node (ref "C13") (pin "2") (pinfunction "2_2") (pintype "passive"))
      (node (ref "C14") (pin "2") (pinfunction "2_2") (pintype "passive"))
      (node (ref "C15") (pin "2") (pinfunction "2_2") (pintype "passive"))
      (node (ref "C16") (pin "2") (pinfunction "2_2") (pintype "passive"))
      (node (ref "C17") (pin "2") (pinfunction "2_2") (pintype "passive"))
      (node (ref "C18") (pin "1") (pinfunction "1_1") (pintype "passive"))
      (node (ref "C19") (pin "2") (pinfunction "2_2") (pintype "passive"))
      (node (ref "C21") (pin "2") (pinfunction "2_2") (pintype "passive"))
      (node (ref "C22") (pin "2") (pinfunction "2_2") (pintype "passive"))
      (node (ref "C25") (pin "1") (pinfunction "1_1") (pintype "passive"))
      (node (ref "C26") (pin "2") (pinfunction "2_2") (pintype "passive"))
      (node (ref "C29") (pin "2") (pinfunction "2_2") (pintype "passive"))
      (node (ref "C30") (pin "1") (pinfunction "1_1") (pintype "passive"))
      (node (ref "C31") (pin "1") (pinfunction "1_1") (pintype "passive"))
      (node (ref "C32") (pin "2") (pinfunction "2_2") (pintype "passive"))
      (node (ref "C33") (pin "2") (pinfunction "2_2") (pintype "passive"))
      (node (ref "C34") (pin "1") (pinfunction "1_1") (pintype "passive"))
      (node (ref "C36") (pin "2") (pinfunction "2_2") (pintype "passive"))
      (node (ref "C37") (pin "2") (pinfunction "2_2") (pintype "passive"))
      (node (ref "C38") (pin "1") (pinfunction "1_1") (pintype "passive"))
      (node (ref "C5") (pin "1") (pinfunction "1_1") (pintype "passive"))
      (node (ref "C6") (pin "2") (pinfunction "2_2") (pintype "passive"))
      (node (ref "C7") (pin "2") (pinfunction "2_2") (pintype "passive"))
      (node (ref "C8") (pin "1") (pinfunction "1_1") (pintype "passive"))
      (node (ref "C9") (pin "2") (pinfunction "2_2") (pintype "passive"))
      (node (ref "JP1") (pin "6") (pinfunction "6_6") (pintype "passive"))
      (node (ref "JP2") (pin "2") (pinfunction "2_2") (pintype "passive"))
      (node (ref "JP7") (pin "P$1") (pinfunction "S_P$1") (pintype "bidirectional"))
      (node (ref "Q1") (pin "5") (pinfunction "B_5") (pintype "passive"))
      (node (ref "Q3") (pin "5") (pinfunction "B_5") (pintype "passive"))
      (node (ref "R15") (pin "2") (pinfunction "2_2") (pintype "passive"))
      (node (ref "R17") (pin "2") (pinfunction "2_2") (pintype "passive"))
      (node (ref "R19") (pin "1") (pinfunction "1_1") (pintype "passive"))
      (node (ref "R20") (pin "1") (pinfunction "1_1") (pintype "passive"))
      (node (ref "R21") (pin "1") (pinfunction "1_1") (pintype "passive"))
      (node (ref "R22") (pin "1") (pinfunction "1_1") (pintype "passive"))
      (node (ref "R27") (pin "1") (pinfunction "1_1") (pintype "passive"))
      (node (ref "R30") (pin "2") (pinfunction "2_2") (pintype "passive"))
      (node (ref "R32") (pin "2") (pinfunction "2_2") (pintype "passive"))
      (node (ref "R34") (pin "2") (pinfunction "2_2") (pintype "passive"))
      (node (ref "R36") (pin "1") (pinfunction "1_1") (pintype "passive"))
      (node (ref "R38") (pin "1") (pinfunction "1_1") (pintype "passive"))
      (node (ref "R41") (pin "1") (pinfunction "1_1") (pintype "passive"))
      (node (ref "R7") (pin "2") (pinfunction "2_2") (pintype "passive"))
      (node (ref "U1") (pin "P$23") (pinfunction "VSS_P$23") (pintype "bidirectional"))
      (node (ref "U1") (pin "P$47") (pinfunction "VSS_P$47") (pintype "bidirectional"))
      (node (ref "U1") (pin "P$8") (pinfunction "VSSA_P$8") (pintype "bidirectional"))
      (node (ref "U11") (pin "P$3") (pinfunction "IN+_P$3") (pintype "bidirectional"))
      (node (ref "U11") (pin "P$5") (pinfunction "IN+_P$5") (pintype "bidirectional"))
      (node (ref "U2") (pin "P$6") (pinfunction "GND_P$6") (pintype "bidirectional"))
      (node (ref "U3") (pin "P$3") (pinfunction "GND_P$3") (pintype "bidirectional"))
      (node (ref "U9") (pin "P$3") (pinfunction "IN+_P$3") (pintype "bidirectional"))
      (node (ref "VR1") (pin "2") (pinfunction "2_2") (pintype "passive"))
      (node (ref "VR2") (pin "2") (pinfunction "2_2") (pintype "passive"))
    )
    (net (code "14") (name "LED") (class "Default")
      (node (ref "LED4") (pin "A") (pinfunction "A_A") (pintype "passive"))
      (node (ref "U1") (pin "P$38") (pinfunction "PA15_P$38") (pintype "bidirectional"))
    )
    (net (code "15") (name "MOSI") (class "Default")
      (node (ref "U1") (pin "P$17") (pinfunction "PA7_P$17") (pintype "bidirectional"))
      (node (ref "U2") (pin "P$8") (pinfunction "DIN_P$8") (pintype "bidirectional"))
    )
    (net (code "16") (name "NRST") (class "Default")
      (node (ref "JP1") (pin "2") (pinfunction "2_2") (pintype "passive"))
      (node (ref "U1") (pin "P$7") (pinfunction "NRST_P$7") (pintype "bidirectional"))
    )
    (net (code "17") (name "NSS") (class "Default")
      (node (ref "U1") (pin "P$14") (pinfunction "PA4_P$14") (pintype "bidirectional"))
      (node (ref "U2") (pin "P$9") (pinfunction "~{SYNC}_P$9") (pintype "bidirectional"))
    )
    (net (code "18") (name "Net-(C2-Pad2)") (class "Default")
      (node (ref "C2") (pin "2") (pinfunction "2_2") (pintype "passive"))
      (node (ref "R26") (pin "1") (pinfunction "1_1") (pintype "passive"))
    )
    (net (code "19") (name "Net-(C4-Pad1)") (class "Default")
      (node (ref "C4") (pin "1") (pinfunction "1_1") (pintype "passive"))
      (node (ref "R3") (pin "1") (pinfunction "1_1") (pintype "passive"))
      (node (ref "R4") (pin "2") (pinfunction "2_2") (pintype "passive"))
    )
    (net (code "20") (name "Net-(C24-Pad1)") (class "Default")
      (node (ref "C24") (pin "1") (pinfunction "1_1") (pintype "passive"))
      (node (ref "R11") (pin "1") (pinfunction "1_1") (pintype "passive"))
      (node (ref "R12") (pin "2") (pinfunction "2_2") (pintype "passive"))
    )
    (net (code "21") (name "Net-(C27-Pad1)") (class "Default")
      (node (ref "C27") (pin "1") (pinfunction "1_1") (pintype "passive"))
      (node (ref "R43") (pin "2") (pinfunction "2_2") (pintype "passive"))
      (node (ref "R44") (pin "1") (pinfunction "1_1") (pintype "passive"))
    )
    (net (code "22") (name "Net-(D1-PadC)") (class "Default")
      (node (ref "D1") (pin "C") (pinfunction "C_C") (pintype "passive"))
      (node (ref "D2") (pin "A") (pinfunction "A_A") (pintype "passive"))
    )
    (net (code "23") (name "Net-(D2-PadC)") (class "Default")
      (node (ref "D2") (pin "C") (pinfunction "C_C") (pintype "passive"))
      (node (ref "D3") (pin "A") (pinfunction "A_A") (pintype "passive"))
    )
    (net (code "24") (name "Net-(D4-PadC)") (class "Default")
      (node (ref "D4") (pin "C") (pinfunction "C_C") (pintype "passive"))
      (node (ref "D5") (pin "A") (pinfunction "A_A") (pintype "passive"))
    )
    (net (code "25") (name "Net-(D5-PadC)") (class "Default")
      (node (ref "D5") (pin "C") (pinfunction "C_C") (pintype "passive"))
      (node (ref "D6") (pin "A") (pinfunction "A_A") (pintype "passive"))
    )
    (net (code "26") (name "Net-(LED1-PadC)") (class "Default")
      (node (ref "LED1") (pin "C") (pinfunction "C_C") (pintype "passive"))
      (node (ref "R19") (pin "2") (pinfunction "2_2") (pintype "passive"))
    )
    (net (code "27") (name "Net-(LED2-PadC)") (class "Default")
      (node (ref "LED2") (pin "C") (pinfunction "C_C") (pintype "passive"))
      (node (ref "R20") (pin "2") (pinfunction "2_2") (pintype "passive"))
    )
    (net (code "28") (name "Net-(LED3-PadA)") (class "Default")
      (node (ref "LED3") (pin "A") (pinfunction "A_A") (pintype "passive"))
      (node (ref "R21") (pin "2") (pinfunction "2_2") (pintype "passive"))
    )
    (net (code "29") (name "Net-(LED4-PadC)") (class "Default")
      (node (ref "LED4") (pin "C") (pinfunction "C_C") (pintype "passive"))
      (node (ref "R22") (pin "2") (pinfunction "2_2") (pintype "passive"))
    )
    (net (code "30") (name "Net-(Q1A-C)") (class "Default")
      (node (ref "C20") (pin "1") (pinfunction "1_1") (pintype "passive"))
      (node (ref "Q1") (pin "6") (pinfunction "C_6") (pintype "passive"))
      (node (ref "R9") (pin "1") (pinfunction "1_1") (pintype "passive"))
      (node (ref "U9") (pin "P$2") (pinfunction "IN-_P$2") (pintype "bidirectional"))
    )
    (net (code "31") (name "Net-(Q1A-E)") (class "Default")
      (node (ref "Q1") (pin "1") (pinfunction "E_1") (pintype "passive"))
      (node (ref "Q1") (pin "4") (pinfunction "E_4") (pintype "passive"))
      (node (ref "R8") (pin "2") (pinfunction "2_2") (pintype "passive"))
    )
    (net (code "32") (name "Net-(Q1B-C)") (class "Default")
      (node (ref "Q1") (pin "3") (pinfunction "C_3") (pintype "passive"))
      (node (ref "Q2") (pin "2") (pinfunction "B_2") (pintype "passive"))
      (node (ref "Q2") (pin "3") (pinfunction "C_3") (pintype "passive"))
      (node (ref "Q2") (pin "5") (pinfunction "B_5") (pintype "passive"))
    )
    (net (code "33") (name "Net-(Q2A-C)") (class "Default")
      (node (ref "Q2") (pin "6") (pinfunction "C_6") (pintype "passive"))
      (node (ref "SJ1") (pin "2") (pinfunction "2_2") (pintype "passive"))
    )
    (net (code "34") (name "Net-(Q2A-E)") (class "Default")
      (node (ref "Q2") (pin "1") (pinfunction "E_1") (pintype "passive"))
      (node (ref "R24") (pin "1") (pinfunction "1_1") (pintype "passive"))
    )
    (net (code "35") (name "Net-(Q2B-E)") (class "Default")
      (node (ref "Q2") (pin "4") (pinfunction "E_4") (pintype "passive"))
      (node (ref "R23") (pin "1") (pinfunction "1_1") (pintype "passive"))
    )
    (net (code "36") (name "Net-(Q3A-C)") (class "Default")
      (node (ref "C1") (pin "1") (pinfunction "1_1") (pintype "passive"))
      (node (ref "Q3") (pin "6") (pinfunction "C_6") (pintype "passive"))
      (node (ref "R28") (pin "1") (pinfunction "1_1") (pintype "passive"))
      (node (ref "U11") (pin "P$6") (pinfunction "IN-_P$6") (pintype "bidirectional"))
    )
    (net (code "37") (name "Net-(Q3A-E)") (class "Default")
      (node (ref "Q3") (pin "1") (pinfunction "E_1") (pintype "passive"))
      (node (ref "Q3") (pin "4") (pinfunction "E_4") (pintype "passive"))
      (node (ref "R14") (pin "2") (pinfunction "2_2") (pintype "passive"))
    )
    (net (code "38") (name "Net-(Q3B-C)") (class "Default")
      (node (ref "Q3") (pin "3") (pinfunction "C_3") (pintype "passive"))
      (node (ref "Q4") (pin "2") (pinfunction "B_2") (pintype "passive"))
      (node (ref "Q4") (pin "3") (pinfunction "C_3") (pintype "passive"))
      (node (ref "Q4") (pin "5") (pinfunction "B_5") (pintype "passive"))
    )
    (net (code "39") (name "Net-(Q4A-C)") (class "Default")
      (node (ref "Q4") (pin "6") (pinfunction "C_6") (pintype "passive"))
      (node (ref "SJ2") (pin "2") (pinfunction "2_2") (pintype "passive"))
    )
    (net (code "40") (name "Net-(Q4A-E)") (class "Default")
      (node (ref "Q4") (pin "1") (pinfunction "E_1") (pintype "passive"))
      (node (ref "R46") (pin "1") (pinfunction "1_1") (pintype "passive"))
    )
    (net (code "41") (name "Net-(Q4B-E)") (class "Default")
      (node (ref "Q4") (pin "4") (pinfunction "E_4") (pintype "passive"))
      (node (ref "R31") (pin "1") (pinfunction "1_1") (pintype "passive"))
    )
    (net (code "42") (name "Net-(R40-Pad1)") (class "Default")
      (node (ref "R40") (pin "1") (pinfunction "1_1") (pintype "passive"))
      (node (ref "R41") (pin "2") (pinfunction "2_2") (pintype "passive"))
      (node (ref "R42") (pin "1") (pinfunction "1_1") (pintype "passive"))
    )
    (net (code "43") (name "Net-(U1-BOOT0)") (class "Default")
      (node (ref "R7") (pin "1") (pinfunction "1_1") (pintype "passive"))
      (node (ref "U1") (pin "P$44") (pinfunction "BOOT0_P$44") (pintype "bidirectional"))
    )
    (net (code "44") (name "Net-(U4A-IN+)") (class "Default")
      (node (ref "C23") (pin "1") (pinfunction "1_1") (pintype "passive"))
      (node (ref "R11") (pin "2") (pinfunction "2_2") (pintype "passive"))
      (node (ref "U4") (pin "P$3") (pinfunction "IN+_P$3") (pintype "bidirectional"))
    )
    (net (code "45") (name "Net-(U4B-IN+)") (class "Default")
      (node (ref "R15") (pin "1") (pinfunction "1_1") (pintype "passive"))
      (node (ref "R16") (pin "2") (pinfunction "2_2") (pintype "passive"))
      (node (ref "U4") (pin "P$5") (pinfunction "IN+_P$5") (pintype "bidirectional"))
    )
    (net (code "46") (name "Net-(U4B-IN-)") (class "Default")
      (node (ref "R10") (pin "2") (pinfunction "2_2") (pintype "passive"))
      (node (ref "R13") (pin "1") (pinfunction "1_1") (pintype "passive"))
      (node (ref "U4") (pin "P$6") (pinfunction "IN-_P$6") (pintype "bidirectional"))
    )
    (net (code "47") (name "Net-(U4B-OUT)") (class "Default")
      (node (ref "R10") (pin "1") (pinfunction "1_1") (pintype "passive"))
      (node (ref "R12") (pin "1") (pinfunction "1_1") (pintype "passive"))
      (node (ref "TP7") (pin "TP") (pinfunction "TP_TP") (pintype "input"))
      (node (ref "U4") (pin "P$7") (pinfunction "OUT_P$7") (pintype "bidirectional"))
    )
    (net (code "48") (name "Net-(U5A-IN-)") (class "Default")
      (node (ref "R39") (pin "1") (pinfunction "1_1") (pintype "passive"))
      (node (ref "R40") (pin "2") (pinfunction "2_2") (pintype "passive"))
      (node (ref "U5") (pin "P$2") (pinfunction "IN-_P$2") (pintype "bidirectional"))
    )
    (net (code "49") (name "Net-(U5A-OUT)") (class "Default")
      (node (ref "R39") (pin "2") (pinfunction "2_2") (pintype "passive"))
      (node (ref "R43") (pin "1") (pinfunction "1_1") (pintype "passive"))
      (node (ref "U5") (pin "P$1") (pinfunction "OUT_P$1") (pintype "bidirectional"))
    )
    (net (code "50") (name "Net-(U5B-IN+)") (class "Default")
      (node (ref "C28") (pin "1") (pinfunction "1_1") (pintype "passive"))
      (node (ref "R44") (pin "2") (pinfunction "2_2") (pintype "passive"))
      (node (ref "U5") (pin "P$5") (pinfunction "IN+_P$5") (pintype "bidirectional"))
    )
    (net (code "51") (name "Net-(U6A-+IN)") (class "Default")
      (node (ref "R26") (pin "2") (pinfunction "2_2") (pintype "passive"))
      (node (ref "R27") (pin "2") (pinfunction "2_2") (pintype "passive"))
      (node (ref "U6") (pin "3") (pinfunction "+IN_3") (pintype "input"))
    )
    (net (code "52") (name "Net-(U6A--IN)") (class "Default")
      (node (ref "R29") (pin "1") (pinfunction "1_1") (pintype "passive"))
      (node (ref "R30") (pin "1") (pinfunction "1_1") (pintype "passive"))
      (node (ref "U6") (pin "4") (pinfunction "-IN_4") (pintype "input"))
    )
    (net (code "53") (name "Net-(U6A-OUT)") (class "Default")
      (node (ref "C35") (pin "1") (pinfunction "1_1") (pintype "passive"))
      (node (ref "U6") (pin "5") (pinfunction "OUT_5") (pintype "output"))
      (node (ref "U7") (pin "P$3") (pinfunction "IN+_P$3") (pintype "bidirectional"))
    )
    (net (code "54") (name "Net-(U6B-+IN)") (class "Default")
      (node (ref "R32") (pin "1") (pinfunction "1_1") (pintype "passive"))
      (node (ref "R33") (pin "2") (pinfunction "2_2") (pintype "passive"))
      (node (ref "U6") (pin "14") (pinfunction "+IN_14") (pintype "input"))
    )
    (net (code "55") (name "Net-(U6B--IN)") (class "Default")
      (node (ref "R34") (pin "1") (pinfunction "1_1") (pintype "passive"))
      (node (ref "R35") (pin "1") (pinfunction "1_1") (pintype "passive"))
      (node (ref "U6") (pin "13") (pinfunction "-IN_13") (pintype "input"))
    )
    (net (code "56") (name "Net-(U6B-OUT)") (class "Default")
      (node (ref "C36") (pin "1") (pinfunction "1_1") (pintype "passive"))
      (node (ref "U6") (pin "12") (pinfunction "OUT_12") (pintype "output"))
      (node (ref "U7") (pin "P$5") (pinfunction "IN+_P$5") (pintype "bidirectional"))
    )
    (net (code "57") (name "Net-(U7A-IN-)") (class "Default")
      (node (ref "R29") (pin "2") (pinfunction "2_2") (pintype "passive"))
      (node (ref "R33") (pin "1") (pinfunction "1_1") (pintype "passive"))
      (node (ref "U7") (pin "P$1") (pinfunction "OUT_P$1") (pintype "bidirectional"))
      (node (ref "U7") (pin "P$2") (pinfunction "IN-_P$2") (pintype "bidirectional"))
    )
    (net (code "58") (name "Net-(U8A-+IN)") (class "Default")
      (node (ref "R25") (pin "1") (pinfunction "1_1") (pintype "passive"))
      (node (ref "U8") (pin "3") (pinfunction "+IN_3") (pintype "input"))
      (node (ref "VR1") (pin "1") (pinfunction "3_1") (pintype "passive"))
    )
    (net (code "59") (name "Net-(U8A--IN)") (class "Default")
      (node (ref "U8") (pin "4") (pinfunction "-IN_4") (pintype "input"))
      (node (ref "VR1") (pin "3") (pinfunction "1_3") (pintype "passive"))
    )
    (net (code "60") (name "Net-(U8A-AMP{slash}BIAS)") (class "Default")
      (node (ref "R45") (pin "1") (pinfunction "1_1") (pintype "passive"))
      (node (ref "U8") (pin "1") (pinfunction "AMP/BIAS_1") (pintype "passive"))
    )
    (net (code "61") (name "Net-(U8A-OUT)") (class "Default")
      (node (ref "R36") (pin "2") (pinfunction "2_2") (pintype "passive"))
      (node (ref "U8") (pin "5") (pinfunction "OUT_5") (pintype "output"))
      (node (ref "U9") (pin "P$5") (pinfunction "IN+_P$5") (pintype "bidirectional"))
    )
    (net (code "62") (name "Net-(U8B-+IN)") (class "Default")
      (node (ref "R2") (pin "2") (pinfunction "2_2") (pintype "passive"))
      (node (ref "U8") (pin "14") (pinfunction "+IN_14") (pintype "input"))
      (node (ref "VR2") (pin "1") (pinfunction "3_1") (pintype "passive"))
    )
    (net (code "63") (name "Net-(U8B--IN)") (class "Default")
      (node (ref "U8") (pin "13") (pinfunction "-IN_13") (pintype "input"))
      (node (ref "VR2") (pin "3") (pinfunction "1_3") (pintype "passive"))
    )
    (net (code "64") (name "Net-(U9A-OUT)") (class "Default")
      (node (ref "C20") (pin "2") (pinfunction "2_2") (pintype "passive"))
      (node (ref "R8") (pin "1") (pinfunction "1_1") (pintype "passive"))
      (node (ref "U9") (pin "P$1") (pinfunction "OUT_P$1") (pintype "bidirectional"))
    )
    (net (code "65") (name "Net-(U9B-IN-)") (class "Default")
      (node (ref "D1") (pin "A") (pinfunction "A_A") (pintype "passive"))
      (node (ref "D6") (pin "C") (pinfunction "C_C") (pintype "passive"))
      (node (ref "R37") (pin "1") (pinfunction "1_1") (pintype "passive"))
      (node (ref "R38") (pin "2") (pinfunction "2_2") (pintype "passive"))
      (node (ref "U9") (pin "P$6") (pinfunction "IN-_P$6") (pintype "bidirectional"))
    )
    (net (code "66") (name "Net-(U9B-OUT)") (class "Default")
      (node (ref "C35") (pin "2") (pinfunction "2_2") (pintype "passive"))
      (node (ref "D3") (pin "C") (pinfunction "C_C") (pintype "passive"))
      (node (ref "D4") (pin "A") (pinfunction "A_A") (pintype "passive"))
      (node (ref "R37") (pin "2") (pinfunction "2_2") (pintype "passive"))
      (node (ref "U9") (pin "P$7") (pinfunction "OUT_P$7") (pintype "bidirectional"))
    )
    (net (code "67") (name "Net-(U10A-IN+)") (class "Default")
      (node (ref "C3") (pin "1") (pinfunction "1_1") (pintype "passive"))
      (node (ref "R3") (pin "2") (pinfunction "2_2") (pintype "passive"))
      (node (ref "U10") (pin "P$3") (pinfunction "IN+_P$3") (pintype "bidirectional"))
    )
    (net (code "68") (name "Net-(U10B-IN+)") (class "Default")
      (node (ref "R17") (pin "1") (pinfunction "1_1") (pintype "passive"))
      (node (ref "R18") (pin "2") (pinfunction "2_2") (pintype "passive"))
      (node (ref "U10") (pin "P$5") (pinfunction "IN+_P$5") (pintype "bidirectional"))
    )
    (net (code "69") (name "Net-(U10B-IN-)") (class "Default")
      (node (ref "R5") (pin "2") (pinfunction "2_2") (pintype "passive"))
      (node (ref "R6") (pin "1") (pinfunction "1_1") (pintype "passive"))
      (node (ref "U10") (pin "P$6") (pinfunction "IN-_P$6") (pintype "bidirectional"))
    )
    (net (code "70") (name "Net-(U10B-OUT)") (class "Default")
      (node (ref "R4") (pin "1") (pinfunction "1_1") (pintype "passive"))
      (node (ref "R5") (pin "1") (pinfunction "1_1") (pintype "passive"))
      (node (ref "TP2") (pin "TP") (pinfunction "TP_TP") (pintype "input"))
      (node (ref "U10") (pin "P$7") (pinfunction "OUT_P$7") (pintype "bidirectional"))
    )
    (net (code "71") (name "Net-(U11A-IN-)") (class "Default")
      (node (ref "R1") (pin "2") (pinfunction "2_2") (pintype "passive"))
      (node (ref "U11") (pin "P$2") (pinfunction "IN-_P$2") (pintype "bidirectional"))
      (node (ref "U8") (pin "12") (pinfunction "OUT_12") (pintype "output"))
    )
    (net (code "72") (name "Net-(U11B-OUT)") (class "Default")
      (node (ref "C1") (pin "2") (pinfunction "2_2") (pintype "passive"))
      (node (ref "R14") (pin "1") (pinfunction "1_1") (pintype "passive"))
      (node (ref "U11") (pin "P$7") (pinfunction "OUT_P$7") (pintype "bidirectional"))
    )
    (net (code "73") (name "OSC0-OUT") (class "Default")
      (node (ref "C2") (pin "1") (pinfunction "1_1") (pintype "passive"))
      (node (ref "JP5") (pin "1") (pinfunction "1_1") (pintype "passive"))
      (node (ref "U2") (pin "P$2") (pinfunction "V_OUTA_P$2") (pintype "bidirectional"))
    )
    (net (code "74") (name "OSC1-OUT") (class "Default")
      (node (ref "JP6") (pin "1") (pinfunction "1_1") (pintype "passive"))
      (node (ref "U2") (pin "P$3") (pinfunction "V_OUTB_P$3") (pintype "bidirectional"))
    )
    (net (code "75") (name "OSC2-OUT") (class "Default")
      (node (ref "JP3") (pin "1") (pinfunction "1_1") (pintype "passive"))
      (node (ref "U2") (pin "P$4") (pinfunction "V_OUTC_P$4") (pintype "bidirectional"))
    )
    (net (code "76") (name "OSC3-OUT") (class "Default")
      (node (ref "JP4") (pin "1") (pinfunction "1_1") (pintype "passive"))
      (node (ref "U2") (pin "P$5") (pinfunction "V_OUTD_P$5") (pintype "bidirectional"))
    )
    (net (code "77") (name "Q-CTRL0") (class "Default")
      (node (ref "JP5") (pin "4") (pinfunction "4_4") (pintype "passive"))
      (node (ref "U1") (pin "P$31") (pinfunction "PA10_P$31") (pintype "bidirectional"))
      (node (ref "U5") (pin "P$3") (pinfunction "IN+_P$3") (pintype "bidirectional"))
    )
    (net (code "78") (name "Q-CTRL0-I") (class "Default")
      (node (ref "C27") (pin "2") (pinfunction "2_2") (pintype "passive"))
      (node (ref "R45") (pin "2") (pinfunction "2_2") (pintype "passive"))
      (node (ref "U5") (pin "P$6") (pinfunction "IN-_P$6") (pintype "bidirectional"))
      (node (ref "U5") (pin "P$7") (pinfunction "OUT_P$7") (pintype "bidirectional"))
    )
    (net (code "79") (name "Q-CTRL1") (class "Default")
      (node (ref "JP6") (pin "4") (pinfunction "4_4") (pintype "passive"))
      (node (ref "U1") (pin "P$11") (pinfunction "PA1_P$11") (pintype "bidirectional"))
    )
    (net (code "80") (name "Q-CTRL2") (class "Default")
      (node (ref "JP3") (pin "4") (pinfunction "4_4") (pintype "passive"))
      (node (ref "U1") (pin "P$40") (pinfunction "PB4_P$40") (pintype "bidirectional"))
    )
    (net (code "81") (name "Q-CTRL3") (class "Default")
      (node (ref "JP4") (pin "4") (pinfunction "4_4") (pintype "passive"))
      (node (ref "U1") (pin "P$19") (pinfunction "PB1_P$19") (pintype "bidirectional"))
    )
    (net (code "82") (name "SCK") (class "Default")
      (node (ref "U1") (pin "P$15") (pinfunction "PA5_P$15") (pintype "bidirectional"))
      (node (ref "U2") (pin "P$10") (pinfunction "SCLK_P$10") (pintype "bidirectional"))
    )
    (net (code "83") (name "SWCLK") (class "Default")
      (node (ref "JP1") (pin "3") (pinfunction "3_3") (pintype "passive"))
      (node (ref "U1") (pin "P$37") (pinfunction "PA14_P$37") (pintype "bidirectional"))
    )
    (net (code "84") (name "SWDIO") (class "Default")
      (node (ref "JP1") (pin "4") (pinfunction "4_4") (pintype "passive"))
      (node (ref "U1") (pin "P$34") (pinfunction "PA13_P$34") (pintype "bidirectional"))
    )
    (net (code "85") (name "SWO") (class "Default")
      (node (ref "JP1") (pin "1") (pinfunction "1_1") (pintype "passive"))
      (node (ref "U1") (pin "P$39") (pinfunction "PB3_P$39") (pintype "bidirectional"))
    )
    (net (code "86") (name "VCA-CTRL0") (class "Default")
      (node (ref "JP5") (pin "2") (pinfunction "2_2") (pintype "passive"))
      (node (ref "U1") (pin "P$29") (pinfunction "PA8_P$29") (pintype "bidirectional"))
    )
    (net (code "87") (name "VCA-CTRL1") (class "Default")
      (node (ref "JP6") (pin "2") (pinfunction "2_2") (pintype "passive"))
      (node (ref "U1") (pin "P$32") (pinfunction "PA11_P$32") (pintype "bidirectional"))
    )
    (net (code "88") (name "VCA-CTRL2") (class "Default")
      (node (ref "JP3") (pin "2") (pinfunction "2_2") (pintype "passive"))
      (node (ref "U1") (pin "P$12") (pinfunction "PA2_P$12") (pintype "bidirectional"))
    )
    (net (code "89") (name "VCA-CTRL3") (class "Default")
      (node (ref "JP4") (pin "2") (pinfunction "2_2") (pintype "passive"))
      (node (ref "U1") (pin "P$41") (pinfunction "PB5_P$41") (pintype "bidirectional"))
    )
    (net (code "90") (name "VCA-OUT0") (class "Default")
      (node (ref "JP7") (pin "P$2") (pinfunction "T_P$2") (pintype "bidirectional"))
      (node (ref "R1") (pin "1") (pinfunction "1_1") (pintype "passive"))
      (node (ref "TP4") (pin "TP") (pinfunction "TP_TP") (pintype "input"))
      (node (ref "U11") (pin "P$1") (pinfunction "OUT_P$1") (pintype "bidirectional"))
    )
    (net (code "91") (name "VCA0-EXP") (class "Default")
      (node (ref "SJ2") (pin "1") (pinfunction "1_1") (pintype "passive"))
      (node (ref "U8") (pin "16") (pinfunction "AMP/BIAS_16") (pintype "passive"))
    )
    (net (code "92") (name "VCA0-LP") (class "Default")
      (node (ref "C4") (pin "2") (pinfunction "2_2") (pintype "passive"))
      (node (ref "Q3") (pin "2") (pinfunction "B_2") (pintype "passive"))
      (node (ref "TP1") (pin "TP") (pinfunction "TP_TP") (pintype "input"))
      (node (ref "U10") (pin "P$1") (pinfunction "OUT_P$1") (pintype "bidirectional"))
      (node (ref "U10") (pin "P$2") (pinfunction "IN-_P$2") (pintype "bidirectional"))
    )
    (net (code "93") (name "unconnected-(JP7-R-PadP$3)") (class "Default")
      (node (ref "JP7") (pin "P$3") (pinfunction "R_P$3") (pintype "bidirectional"))
    )
    (net (code "94") (name "unconnected-(SW1-PadP$3)") (class "Default")
      (node (ref "SW1") (pin "P$3") (pinfunction "P$3_P$3") (pintype "bidirectional"))
    )
    (net (code "95") (name "unconnected-(SW1-PadP$6)") (class "Default")
      (node (ref "SW1") (pin "P$6") (pinfunction "P$6_P$6") (pintype "bidirectional"))
    )
    (net (code "96") (name "unconnected-(U1-PA6-PadP$16)") (class "Default")
      (node (ref "U1") (pin "P$16") (pinfunction "PA6_P$16") (pintype "bidirectional"))
    )
    (net (code "97") (name "unconnected-(U1-PA12-PadP$33)") (class "Default")
      (node (ref "U1") (pin "P$33") (pinfunction "PA12_P$33") (pintype "bidirectional"))
    )
    (net (code "98") (name "unconnected-(U1-PB2-PadP$20)") (class "Default")
      (node (ref "U1") (pin "P$20") (pinfunction "PB2_P$20") (pintype "bidirectional"))
    )
    (net (code "99") (name "unconnected-(U1-PB6-PadP$42)") (class "Default")
      (node (ref "U1") (pin "P$42") (pinfunction "PB6_P$42") (pintype "bidirectional"))
    )
    (net (code "100") (name "unconnected-(U1-PB7-PadP$43)") (class "Default")
      (node (ref "U1") (pin "P$43") (pinfunction "PB7_P$43") (pintype "bidirectional"))
    )
    (net (code "101") (name "unconnected-(U1-PB8-PadP$45)") (class "Default")
      (node (ref "U1") (pin "P$45") (pinfunction "PB8_P$45") (pintype "bidirectional"))
    )
    (net (code "102") (name "unconnected-(U1-PB9-PadP$46)") (class "Default")
      (node (ref "U1") (pin "P$46") (pinfunction "PB9_P$46") (pintype "bidirectional"))
    )
    (net (code "103") (name "unconnected-(U1-PB10-PadP$21)") (class "Default")
      (node (ref "U1") (pin "P$21") (pinfunction "PB10_P$21") (pintype "bidirectional"))
    )
    (net (code "104") (name "unconnected-(U1-PB11-PadP$22)") (class "Default")
      (node (ref "U1") (pin "P$22") (pinfunction "PB11_P$22") (pintype "bidirectional"))
    )
    (net (code "105") (name "unconnected-(U1-PB12-PadP$25)") (class "Default")
      (node (ref "U1") (pin "P$25") (pinfunction "PB12_P$25") (pintype "bidirectional"))
    )
    (net (code "106") (name "unconnected-(U1-PB13-PadP$26)") (class "Default")
      (node (ref "U1") (pin "P$26") (pinfunction "PB13_P$26") (pintype "bidirectional"))
    )
    (net (code "107") (name "unconnected-(U1-PB14-PadP$27)") (class "Default")
      (node (ref "U1") (pin "P$27") (pinfunction "PB14_P$27") (pintype "bidirectional"))
    )
    (net (code "108") (name "unconnected-(U1-PB15-PadP$28)") (class "Default")
      (node (ref "U1") (pin "P$28") (pinfunction "PB15_P$28") (pintype "bidirectional"))
    )
    (net (code "109") (name "unconnected-(U1-PC13-PadP$2)") (class "Default")
      (node (ref "U1") (pin "P$2") (pinfunction "PC13_P$2") (pintype "bidirectional"))
    )
    (net (code "110") (name "unconnected-(U1-PC14-OSC32_IN-PadP$3)") (class "Default")
      (node (ref "U1") (pin "P$3") (pinfunction "PC14-OSC32_IN_P$3") (pintype "bidirectional"))
    )
    (net (code "111") (name "unconnected-(U1-PC15-OSC32_OUT-PadP$4)") (class "Default")
      (node (ref "U1") (pin "P$4") (pinfunction "PC15-OSC32_OUT_P$4") (pintype "bidirectional"))
    )
    (net (code "112") (name "unconnected-(U1-PF0-OSC_IN-PadP$5)") (class "Default")
      (node (ref "U1") (pin "P$5") (pinfunction "PF0-OSC_IN_P$5") (pintype "bidirectional"))
    )
    (net (code "113") (name "unconnected-(U1-PF1-OSC_OUT-PadP$6)") (class "Default")
      (node (ref "U1") (pin "P$6") (pinfunction "PF1-OSC_OUT_P$6") (pintype "bidirectional"))
    )
    (net (code "114") (name "unconnected-(U1-PF6-PadP$35)") (class "Default")
      (node (ref "U1") (pin "P$35") (pinfunction "PF6_P$35") (pintype "bidirectional"))
    )
    (net (code "115") (name "unconnected-(U1-PF7-PadP$36)") (class "Default")
      (node (ref "U1") (pin "P$36") (pinfunction "PF7_P$36") (pintype "bidirectional"))
    )
    (net (code "116") (name "unconnected-(U1-VBAT-PadP$1)") (class "Default")
      (node (ref "U1") (pin "P$1") (pinfunction "VBAT_P$1") (pintype "bidirectional"))
    )
    (net (code "117") (name "unconnected-(U6A-BUFF{slash}IN-Pad7)") (class "Default")
      (node (ref "U6") (pin "7") (pinfunction "BUFF/IN_7") (pintype "input"))
    )
    (net (code "118") (name "unconnected-(U6A-BUFF{slash}OUT-Pad8)") (class "Default")
      (node (ref "U6") (pin "8") (pinfunction "BUFF/OUT_8") (pintype "output"))
    )
    (net (code "119") (name "unconnected-(U6A-DIODE{slash}BIAS-Pad2)") (class "Default")
      (node (ref "U6") (pin "2") (pinfunction "DIODE/BIAS_2") (pintype "passive"))
    )
    (net (code "120") (name "unconnected-(U6B-BUFF{slash}IN-Pad10)") (class "Default")
      (node (ref "U6") (pin "10") (pinfunction "BUFF/IN_10") (pintype "input"))
    )
    (net (code "121") (name "unconnected-(U6B-BUFF{slash}OUT-Pad9)") (class "Default")
      (node (ref "U6") (pin "9") (pinfunction "BUFF/OUT_9") (pintype "output"))
    )
    (net (code "122") (name "unconnected-(U6B-DIODE{slash}BIAS-Pad15)") (class "Default")
      (node (ref "U6") (pin "15") (pinfunction "DIODE/BIAS_15") (pintype "passive"))
    )
    (net (code "123") (name "unconnected-(U8A-BUFF{slash}IN-Pad7)") (class "Default")
      (node (ref "U8") (pin "7") (pinfunction "BUFF/IN_7") (pintype "input"))
    )
    (net (code "124") (name "unconnected-(U8A-BUFF{slash}OUT-Pad8)") (class "Default")
      (node (ref "U8") (pin "8") (pinfunction "BUFF/OUT_8") (pintype "output"))
    )
    (net (code "125") (name "unconnected-(U8A-DIODE{slash}BIAS-Pad2)") (class "Default")
      (node (ref "U8") (pin "2") (pinfunction "DIODE/BIAS_2") (pintype "passive"))
    )
    (net (code "126") (name "unconnected-(U8B-BUFF{slash}IN-Pad10)") (class "Default")
      (node (ref "U8") (pin "10") (pinfunction "BUFF/IN_10") (pintype "input"))
    )
    (net (code "127") (name "unconnected-(U8B-BUFF{slash}OUT-Pad9)") (class "Default")
      (node (ref "U8") (pin "9") (pinfunction "BUFF/OUT_9") (pintype "output"))
    )
    (net (code "128") (name "unconnected-(U8B-DIODE{slash}BIAS-Pad15)") (class "Default")
      (node (ref "U8") (pin "15") (pinfunction "DIODE/BIAS_15") (pintype "passive"))
    )
  )
)
